# vc_reverb.net
KiCad netlist of a schematic drawn in EAGLE
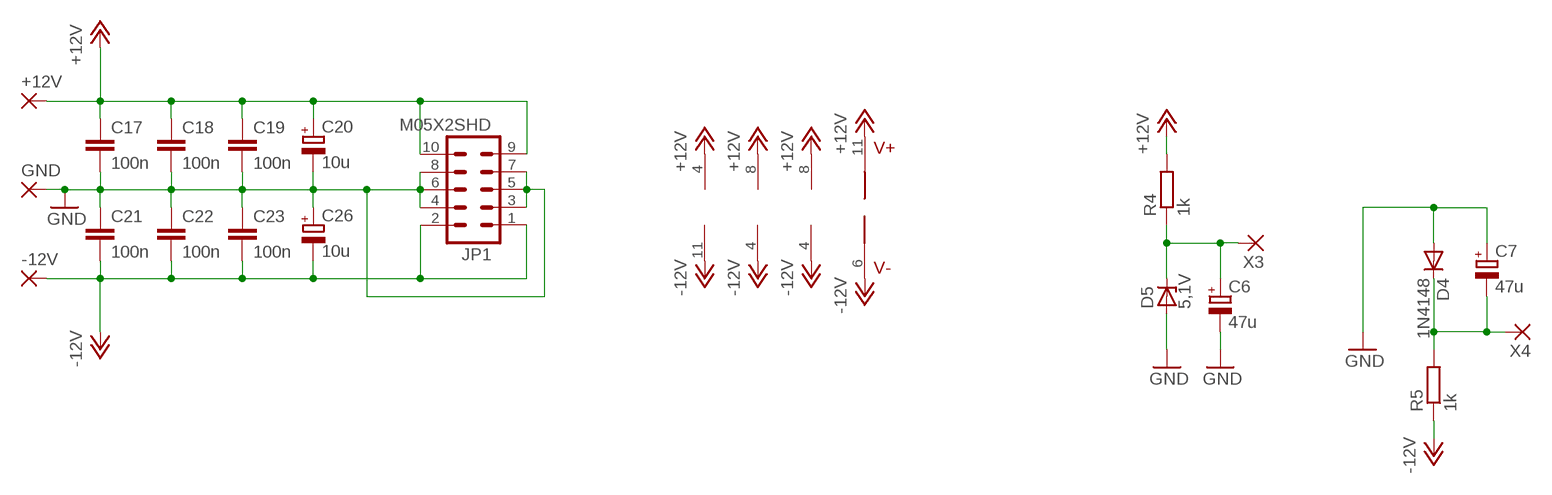
[diagram p0: schematic, sheet 1]
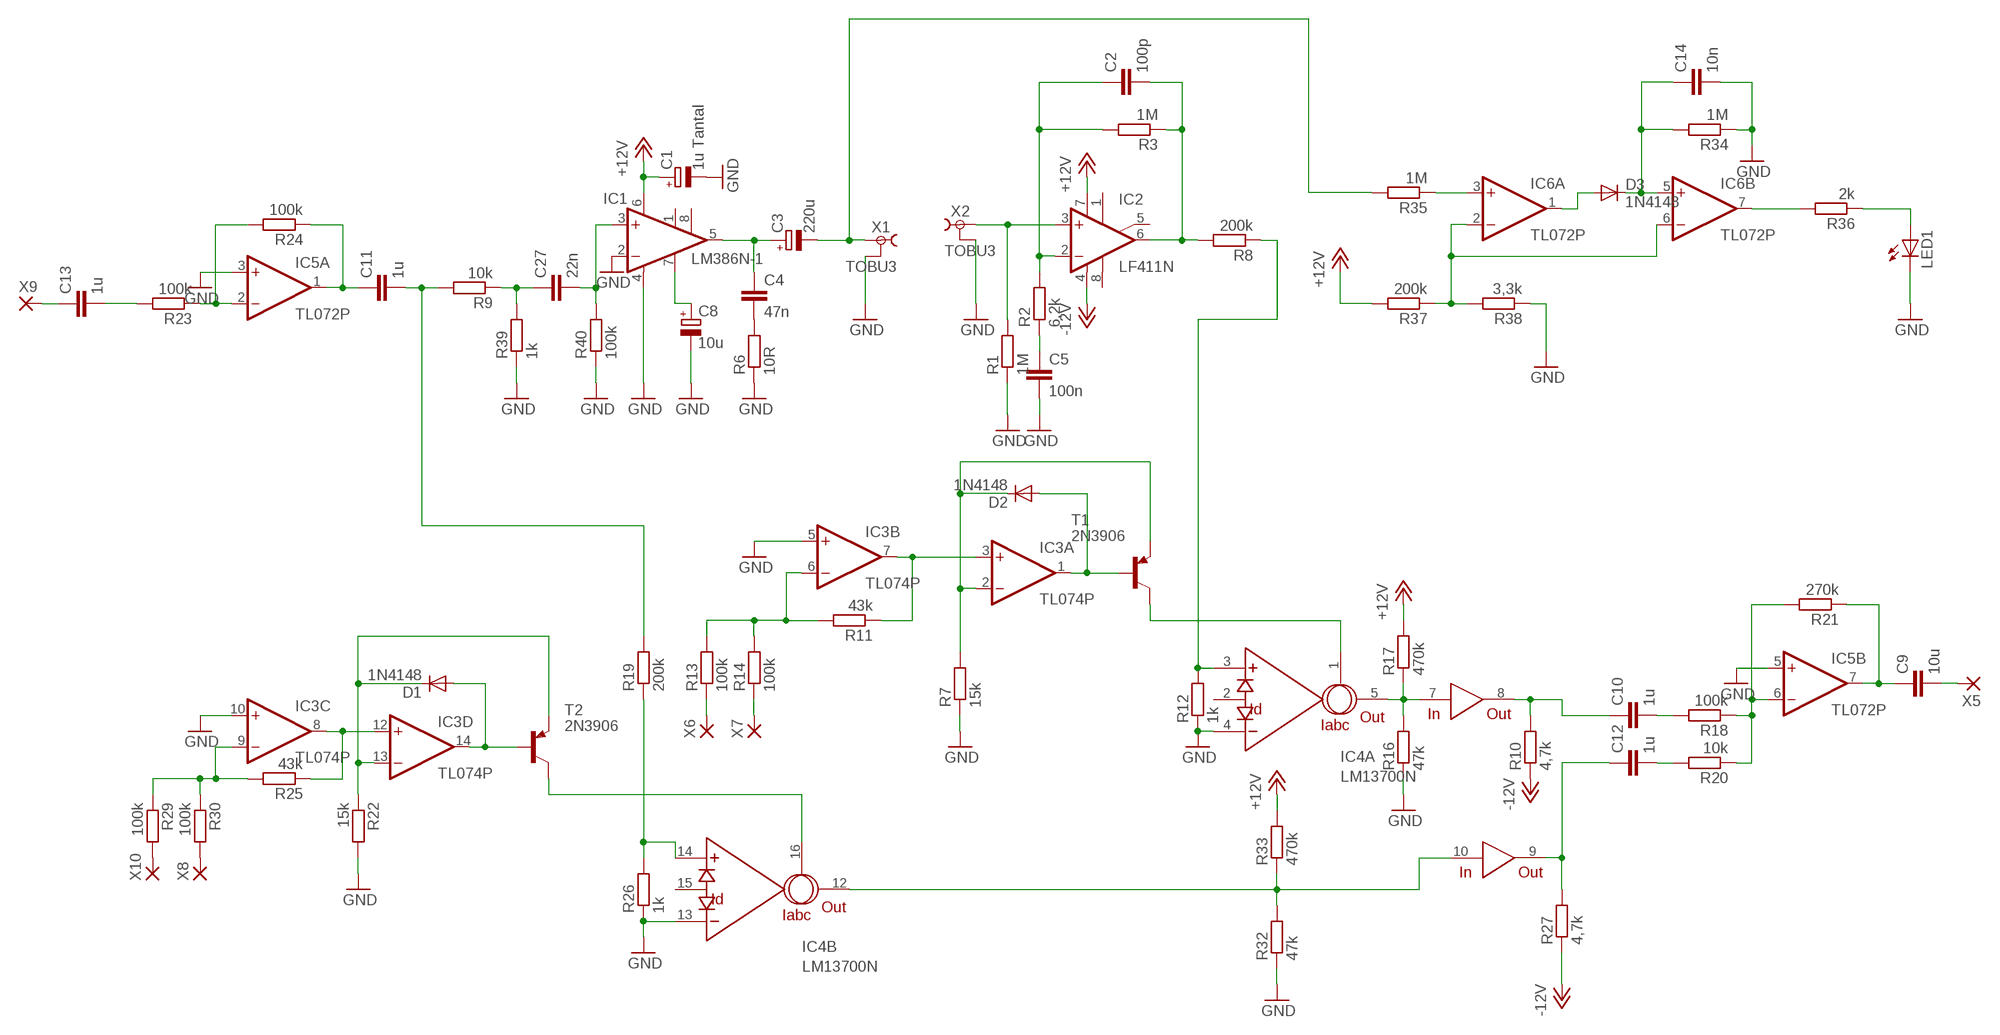
[diagram p1: schematic, sheet 2]

(export (version "E")
  (design (tool "Eeschema 10.0.6"))
  (components
    (comp (ref "C1")
      (value "1u Tantal")
      (footprint "eagle-import:E2-5")
      (libsource (lib "eagle-import") (part "CPOL-EUE2-5"))
    )
    (comp (ref "C2")
      (value "100p")
      (footprint "eagle-import:C050-035X075")
      (libsource (lib "eagle-import") (part "C-EU050-035X075"))
    )
    (comp (ref "C3")
      (value "220u")
      (footprint "eagle-import:E3,5-8")
      (libsource (lib "eagle-import") (part "CPOL-EUE3.5-8"))
    )
    (comp (ref "C4")
      (value "47n")
      (footprint "eagle-import:C050-035X075")
      (libsource (lib "eagle-import") (part "C-EU050-035X075"))
    )
    (comp (ref "C5")
      (value "100n")
      (footprint "eagle-import:C050-035X075")
      (libsource (lib "eagle-import") (part "C-EU050-035X075"))
    )
    (comp (ref "C8")
      (value "10u")
      (footprint "eagle-import:E2-5")
      (libsource (lib "eagle-import") (part "CPOL-EUE2-5"))
    )
    (comp (ref "C9")
      (value "10u")
      (footprint "eagle-import:C050-075X075")
      (libsource (lib "eagle-import") (part "C-EU050-075X075"))
    )
    (comp (ref "C10")
      (value "1u")
      (footprint "eagle-import:C050-050X075")
      (libsource (lib "eagle-import") (part "C-EU050-050X075"))
    )
    (comp (ref "C11")
      (value "1u")
      (footprint "eagle-import:C050-050X075")
      (libsource (lib "eagle-import") (part "C-EU050-050X075"))
    )
    (comp (ref "C12")
      (value "1u")
      (footprint "eagle-import:C050-050X075")
      (libsource (lib "eagle-import") (part "C-EU050-050X075"))
    )
    (comp (ref "C13")
      (value "1u")
      (footprint "eagle-import:C050-050X075")
      (libsource (lib "eagle-import") (part "C-EU050-050X075"))
    )
    (comp (ref "C14")
      (value "10n")
      (footprint "eagle-import:C050-030X075")
      (libsource (lib "eagle-import") (part "C-EU050-030X075"))
    )
    (comp (ref "C27")
      (value "22n")
      (footprint "eagle-import:C050-035X075")
      (libsource (lib "eagle-import") (part "C-EU050-035X075"))
    )
    (comp (ref "D1")
      (value "1N4148")
      (footprint "eagle-import:DO35-7")
      (libsource (lib "eagle-import") (part "1N4148DO35-7"))
    )
    (comp (ref "D2")
      (value "1N4148")
      (footprint "eagle-import:DO35-7")
      (libsource (lib "eagle-import") (part "1N4148DO35-7"))
    )
    (comp (ref "D3")
      (value "1N4148")
      (footprint "eagle-import:DO35-7")
      (libsource (lib "eagle-import") (part "1N4148DO35-7"))
    )
    (comp (ref "IC1")
      (value "LM386N-1")
      (footprint "eagle-import:DIL08")
      (libsource (lib "eagle-import") (part "LM386?-N1"))
    )
    (comp (ref "IC2")
      (value "LF411N")
      (footprint "eagle-import:DIL08")
      (libsource (lib "eagle-import") (part "LF411N"))
    )
    (comp (ref "IC3")
      (value "TL074P")
      (footprint "eagle-import:DIL14")
      (libsource (lib "eagle-import") (part "TL074P"))
    )
    (comp (ref "IC4")
      (value "LM13700N")
      (footprint "eagle-import:DIL16")
      (libsource (lib "eagle-import") (part "LM13700N"))
    )
    (comp (ref "IC5")
      (value "TL072P")
      (footprint "eagle-import:DIL08")
      (libsource (lib "eagle-import") (part "TL072P"))
    )
    (comp (ref "IC6")
      (value "TL072P")
      (footprint "eagle-import:DIL08")
      (libsource (lib "eagle-import") (part "TL072P"))
    )
    (comp (ref "LED1")
      (value "LED5MM")
      (footprint "eagle-import:LED5MM")
      (libsource (lib "eagle-import") (part "LED5MM"))
    )
    (comp (ref "R1")
      (value "1M")
      (footprint "eagle-import:0309V")
      (libsource (lib "eagle-import") (part "R-EU_0309/V"))
    )
    (comp (ref "R2")
      (value "6,2k")
      (footprint "eagle-import:0309V")
      (libsource (lib "eagle-import") (part "R-EU_0309/V"))
    )
    (comp (ref "R3")
      (value "1M")
      (footprint "eagle-import:0309V")
      (libsource (lib "eagle-import") (part "R-EU_0309/V"))
    )
    (comp (ref "R6")
      (value "10R")
      (footprint "eagle-import:0309V")
      (libsource (lib "eagle-import") (part "R-EU_0309/V"))
    )
    (comp (ref "R7")
      (value "15k")
      (footprint "eagle-import:0309V")
      (libsource (lib "eagle-import") (part "R-EU_0309/V"))
    )
    (comp (ref "R8")
      (value "200k")
      (footprint "eagle-import:0309V")
      (libsource (lib "eagle-import") (part "R-EU_0309/V"))
    )
    (comp (ref "R9")
      (value "10k")
      (footprint "eagle-import:0309V")
      (libsource (lib "eagle-import") (part "R-EU_0309/V"))
    )
    (comp (ref "R10")
      (value "4,7k")
      (footprint "eagle-import:0309V")
      (libsource (lib "eagle-import") (part "R-EU_0309/V"))
    )
    (comp (ref "R11")
      (value "43k")
      (footprint "eagle-import:0309V")
      (libsource (lib "eagle-import") (part "R-EU_0309/V"))
    )
    (comp (ref "R12")
      (value "1k")
      (footprint "eagle-import:0309V")
      (libsource (lib "eagle-import") (part "R-EU_0309/V"))
    )
    (comp (ref "R13")
      (value "100k")
      (footprint "eagle-import:0309V")
      (libsource (lib "eagle-import") (part "R-EU_0309/V"))
    )
    (comp (ref "R14")
      (value "100k")
      (footprint "eagle-import:0309V")
      (libsource (lib "eagle-import") (part "R-EU_0309/V"))
    )
    (comp (ref "R16")
      (value "47k")
      (footprint "eagle-import:0309V")
      (libsource (lib "eagle-import") (part "R-EU_0309/V"))
    )
    (comp (ref "R17")
      (value "470k")
      (footprint "eagle-import:0309V")
      (libsource (lib "eagle-import") (part "R-EU_0309/V"))
    )
    (comp (ref "R18")
      (value "100k")
      (footprint "eagle-import:0309V")
      (libsource (lib "eagle-import") (part "R-EU_0309/V"))
    )
    (comp (ref "R19")
      (value "200k")
      (footprint "eagle-import:0309_10")
      (libsource (lib "eagle-import") (part "R-EU_0309/10"))
    )
    (comp (ref "R20")
      (value "10k")
      (footprint "eagle-import:0309V")
      (libsource (lib "eagle-import") (part "R-EU_0309/V"))
    )
    (comp (ref "R21")
      (value "270k")
      (footprint "eagle-import:0309V")
      (libsource (lib "eagle-import") (part "R-EU_0309/V"))
    )
    (comp (ref "R22")
      (value "15k")
      (footprint "eagle-import:0309V")
      (libsource (lib "eagle-import") (part "R-EU_0309/V"))
    )
    (comp (ref "R23")
      (value "100k")
      (footprint "eagle-import:0309V")
      (libsource (lib "eagle-import") (part "R-EU_0309/V"))
    )
    (comp (ref "R24")
      (value "100k")
      (footprint "eagle-import:0309V")
      (libsource (lib "eagle-import") (part "R-EU_0309/V"))
    )
    (comp (ref "R25")
      (value "43k")
      (footprint "eagle-import:0309V")
      (libsource (lib "eagle-import") (part "R-EU_0309/V"))
    )
    (comp (ref "R26")
      (value "1k")
      (footprint "eagle-import:0309V")
      (libsource (lib "eagle-import") (part "R-EU_0309/V"))
    )
    (comp (ref "R27")
      (value "4,7k")
      (footprint "eagle-import:0309V")
      (libsource (lib "eagle-import") (part "R-EU_0309/V"))
    )
    (comp (ref "R29")
      (value "100k")
      (footprint "eagle-import:0309V")
      (libsource (lib "eagle-import") (part "R-EU_0309/V"))
    )
    (comp (ref "R30")
      (value "100k")
      (footprint "eagle-import:0309V")
      (libsource (lib "eagle-import") (part "R-EU_0309/V"))
    )
    (comp (ref "R32")
      (value "47k")
      (footprint "eagle-import:0309V")
      (libsource (lib "eagle-import") (part "R-EU_0309/V"))
    )
    (comp (ref "R33")
      (value "470k")
      (footprint "eagle-import:0309V")
      (libsource (lib "eagle-import") (part "R-EU_0309/V"))
    )
    (comp (ref "R34")
      (value "1M")
      (footprint "eagle-import:0309V")
      (libsource (lib "eagle-import") (part "R-EU_0309/V"))
    )
    (comp (ref "R35")
      (value "1M")
      (footprint "eagle-import:0309V")
      (libsource (lib "eagle-import") (part "R-EU_0309/V"))
    )
    (comp (ref "R36")
      (value "2k")
      (footprint "eagle-import:0309V")
      (libsource (lib "eagle-import") (part "R-EU_0309/V"))
    )
    (comp (ref "R37")
      (value "200k")
      (footprint "eagle-import:0309V")
      (libsource (lib "eagle-import") (part "R-EU_0309/V"))
    )
    (comp (ref "R38")
      (value "3,3k")
      (footprint "eagle-import:0309V")
      (libsource (lib "eagle-import") (part "R-EU_0309/V"))
    )
    (comp (ref "R39")
      (value "1k")
      (footprint "eagle-import:0309V")
      (libsource (lib "eagle-import") (part "R-EU_0309/V"))
    )
    (comp (ref "R40")
      (value "100k")
      (footprint "eagle-import:0309V")
      (libsource (lib "eagle-import") (part "R-EU_0309/V"))
    )
    (comp (ref "T1")
      (value "2N3906")
      (footprint "eagle-import:TO92-EBC")
      (libsource (lib "eagle-import") (part "-PNP-TO92-EBC2N3906"))
    )
    (comp (ref "T2")
      (value "2N3906")
      (footprint "eagle-import:TO92-EBC")
      (libsource (lib "eagle-import") (part "-PNP-TO92-EBC2N3906"))
    )
    (comp (ref "X1")
      (value "TOBU3")
      (footprint "eagle-import:TOBU3")
      (fields (field (name "MF") "FARNELL") (field (name "MPN") "TOBU 3"))
      (libsource (lib "eagle-import") (part "TOBU3"))
    )
    (comp (ref "X2")
      (value "TOBU3")
      (footprint "eagle-import:TOBU3")
      (fields (field (name "MF") "FARNELL") (field (name "MPN") "TOBU 3"))
      (libsource (lib "eagle-import") (part "TOBU3"))
    )
    (comp (ref "X5")
      (value "2,54/1,0")
      (footprint "eagle-import:2,54_1,0")
      (libsource (lib "eagle-import") (part "2,54/1,0"))
    )
    (comp (ref "X6")
      (value "2,54/1,0")
      (footprint "eagle-import:2,54_1,0")
      (libsource (lib "eagle-import") (part "2,54/1,0"))
    )
    (comp (ref "X7")
      (value "2,54/1,0")
      (footprint "eagle-import:2,54_1,0")
      (libsource (lib "eagle-import") (part "2,54/1,0"))
    )
    (comp (ref "X8")
      (value "2,54/1,0")
      (footprint "eagle-import:2,54_1,0")
      (libsource (lib "eagle-import") (part "2,54/1,0"))
    )
    (comp (ref "X9")
      (value "2,54/1,0")
      (footprint "eagle-import:2,54_1,0")
      (libsource (lib "eagle-import") (part "2,54/1,0"))
    )
    (comp (ref "X10")
      (value "2,54/1,0")
      (footprint "eagle-import:2,54_1,0")
      (libsource (lib "eagle-import") (part "2,54/1,0"))
    )
    (comp (ref "+12V")
      (value "2,54/1,0")
      (footprint "eagle-import:2,54_1,0")
      (libsource (lib "eagle-import") (part "2,54/1,0"))
    )
    (comp (ref "-12V")
      (value "2,54/1,0")
      (footprint "eagle-import:2,54_1,0")
      (libsource (lib "eagle-import") (part "2,54/1,0"))
    )
    (comp (ref "C6")
      (value "47u")
      (footprint "eagle-import:E2-5")
      (libsource (lib "eagle-import") (part "CPOL-EUE2-5"))
    )
    (comp (ref "C7")
      (value "47u")
      (footprint "eagle-import:E2-5")
      (libsource (lib "eagle-import") (part "CPOL-EUE2-5"))
    )
    (comp (ref "C17")
      (value "100n")
      (footprint "eagle-import:C025-025X050")
      (libsource (lib "eagle-import") (part "C-EU025-025X050"))
    )
    (comp (ref "C18")
      (value "100n")
      (footprint "eagle-import:C050-035X075")
      (libsource (lib "eagle-import") (part "C-EU050-035X075"))
    )
    (comp (ref "C19")
      (value "100n")
      (footprint "eagle-import:C025-025X050")
      (libsource (lib "eagle-import") (part "C-EU025-025X050"))
    )
    (comp (ref "C20")
      (value "10u")
      (footprint "eagle-import:E2-5")
      (libsource (lib "eagle-import") (part "CPOL-EUE2-5"))
    )
    (comp (ref "C21")
      (value "100n")
      (footprint "eagle-import:C025-025X050")
      (libsource (lib "eagle-import") (part "C-EU025-025X050"))
    )
    (comp (ref "C22")
      (value "100n")
      (footprint "eagle-import:C050-035X075")
      (libsource (lib "eagle-import") (part "C-EU050-035X075"))
    )
    (comp (ref "C23")
      (value "100n")
      (footprint "eagle-import:C025-025X050")
      (libsource (lib "eagle-import") (part "C-EU025-025X050"))
    )
    (comp (ref "C26")
      (value "10u")
      (footprint "eagle-import:E2-5")
      (libsource (lib "eagle-import") (part "CPOL-EUE2-5"))
    )
    (comp (ref "D4")
      (value "1N4148")
      (footprint "eagle-import:DO35-7")
      (libsource (lib "eagle-import") (part "1N4148DO35-7"))
    )
    (comp (ref "D5")
      (value "5,1V")
      (footprint "eagle-import:DO34Z7")
      (libsource (lib "eagle-import") (part "ZENER-DIODEDO34-7"))
    )
    (comp (ref "GND")
      (value "2,54/1,0")
      (footprint "eagle-import:2,54_1,0")
      (libsource (lib "eagle-import") (part "2,54/1,0"))
    )
    (comp (ref "JP1")
      (value "M05X2SHD")
      (footprint "eagle-import:2X5-SHROUDED")
      (libsource (lib "eagle-import") (part "M05X2SHD"))
    )
    (comp (ref "R4")
      (value "1k")
      (footprint "eagle-import:0309V")
      (libsource (lib "eagle-import") (part "R-EU_0309/V"))
    )
    (comp (ref "R5")
      (value "1k")
      (footprint "eagle-import:0309V")
      (libsource (lib "eagle-import") (part "R-EU_0309/V"))
    )
    (comp (ref "X3")
      (value "2,54/1,0")
      (footprint "eagle-import:2,54_1,0")
      (libsource (lib "eagle-import") (part "2,54/1,0"))
    )
    (comp (ref "X4")
      (value "2,54/1,0")
      (footprint "eagle-import:2,54_1,0")
      (libsource (lib "eagle-import") (part "2,54/1,0"))
    )
  )
  (nets
    (net (code "1") (name "+12V") (class "Default")
      (node (ref "+12V") (pin "1") (pinfunction "P_1") (pintype "passive"))
      (node (ref "C1") (pin "+") (pinfunction "+_+") (pintype "passive"))
      (node (ref "C17") (pin "1") (pinfunction "1_1") (pintype "passive"))
      (node (ref "C18") (pin "1") (pinfunction "1_1") (pintype "passive"))
      (node (ref "C19") (pin "1") (pinfunction "1_1") (pintype "passive"))
      (node (ref "C20") (pin "+") (pinfunction "+_+") (pintype "passive"))
      (node (ref "IC1") (pin "6") (pinfunction "VS_6") (pintype "power_in"))
      (node (ref "IC2") (pin "7") (pinfunction "V+_7") (pintype "power_in"))
      (node (ref "IC3") (pin "4") (pinfunction "V+_4") (pintype "power_in"))
      (node (ref "IC4") (pin "11") (pinfunction "V+_11") (pintype "bidirectional"))
      (node (ref "IC5") (pin "8") (pinfunction "V+_8") (pintype "power_in"))
      (node (ref "IC6") (pin "8") (pinfunction "V+_8") (pintype "power_in"))
      (node (ref "JP1") (pin "10") (pinfunction "10_10") (pintype "passive"))
      (node (ref "JP1") (pin "9") (pinfunction "9_9") (pintype "passive"))
      (node (ref "R17") (pin "2") (pinfunction "2_2") (pintype "passive"))
      (node (ref "R33") (pin "2") (pinfunction "2_2") (pintype "passive"))
      (node (ref "R37") (pin "2") (pinfunction "2_2") (pintype "passive"))
      (node (ref "R4") (pin "2") (pinfunction "2_2") (pintype "passive"))
    )
    (net (code "2") (name "-12V") (class "Default")
      (node (ref "-12V") (pin "1") (pinfunction "P_1") (pintype "passive"))
      (node (ref "C21") (pin "2") (pinfunction "2_2") (pintype "passive"))
      (node (ref "C22") (pin "2") (pinfunction "2_2") (pintype "passive"))
      (node (ref "C23") (pin "2") (pinfunction "2_2") (pintype "passive"))
      (node (ref "C26") (pin "-") (pinfunction "-_-") (pintype "passive"))
      (node (ref "IC2") (pin "4") (pinfunction "V-_4") (pintype "power_in"))
      (node (ref "IC3") (pin "11") (pinfunction "V-_11") (pintype "power_in"))
      (node (ref "IC4") (pin "6") (pinfunction "V-_6") (pintype "bidirectional"))
      (node (ref "IC5") (pin "4") (pinfunction "V-_4") (pintype "power_in"))
      (node (ref "IC6") (pin "4") (pinfunction "V-_4") (pintype "power_in"))
      (node (ref "JP1") (pin "1") (pinfunction "1_1") (pintype "passive"))
      (node (ref "JP1") (pin "2") (pinfunction "2_2") (pintype "passive"))
      (node (ref "R10") (pin "1") (pinfunction "1_1") (pintype "passive"))
      (node (ref "R27") (pin "1") (pinfunction "1_1") (pintype "passive"))
      (node (ref "R5") (pin "1") (pinfunction "1_1") (pintype "passive"))
    )
    (net (code "3") (name "GND") (class "Default")
      (node (ref "C1") (pin "-") (pinfunction "-_-") (pintype "passive"))
      (node (ref "C14") (pin "2") (pinfunction "2_2") (pintype "passive"))
      (node (ref "C17") (pin "2") (pinfunction "2_2") (pintype "passive"))
      (node (ref "C18") (pin "2") (pinfunction "2_2") (pintype "passive"))
      (node (ref "C19") (pin "2") (pinfunction "2_2") (pintype "passive"))
      (node (ref "C20") (pin "-") (pinfunction "-_-") (pintype "passive"))
      (node (ref "C21") (pin "1") (pinfunction "1_1") (pintype "passive"))
      (node (ref "C22") (pin "1") (pinfunction "1_1") (pintype "passive"))
      (node (ref "C23") (pin "1") (pinfunction "1_1") (pintype "passive"))
      (node (ref "C26") (pin "+") (pinfunction "+_+") (pintype "passive"))
      (node (ref "C5") (pin "2") (pinfunction "2_2") (pintype "passive"))
      (node (ref "C6") (pin "-") (pinfunction "-_-") (pintype "passive"))
      (node (ref "C7") (pin "+") (pinfunction "+_+") (pintype "passive"))
      (node (ref "C8") (pin "-") (pinfunction "-_-") (pintype "passive"))
      (node (ref "D4") (pin "A") (pinfunction "A_A") (pintype "passive"))
      (node (ref "D5") (pin "A") (pinfunction "A_A") (pintype "passive"))
      (node (ref "GND") (pin "1") (pinfunction "P_1") (pintype "passive"))
      (node (ref "IC1") (pin "2") (pinfunction "-IN_2") (pintype "input"))
      (node (ref "IC1") (pin "4") (pinfunction "GND_4") (pintype "power_in"))
      (node (ref "IC3") (pin "10") (pinfunction "+IN_10") (pintype "input"))
      (node (ref "IC3") (pin "5") (pinfunction "+IN_5") (pintype "input"))
      (node (ref "IC4") (pin "13") (pinfunction "-IN_13") (pintype "bidirectional"))
      (node (ref "IC4") (pin "4") (pinfunction "-IN_4") (pintype "bidirectional"))
      (node (ref "IC5") (pin "3") (pinfunction "+IN_3") (pintype "input"))
      (node (ref "IC5") (pin "5") (pinfunction "+IN_5") (pintype "input"))
      (node (ref "JP1") (pin "3") (pinfunction "3_3") (pintype "passive"))
      (node (ref "JP1") (pin "4") (pinfunction "4_4") (pintype "passive"))
      (node (ref "JP1") (pin "5") (pinfunction "5_5") (pintype "passive"))
      (node (ref "JP1") (pin "6") (pinfunction "6_6") (pintype "passive"))
      (node (ref "JP1") (pin "7") (pinfunction "7_7") (pintype "passive"))
      (node (ref "JP1") (pin "8") (pinfunction "8_8") (pintype "passive"))
      (node (ref "LED1") (pin "K") (pinfunction "C_K") (pintype "passive"))
      (node (ref "R1") (pin "1") (pinfunction "1_1") (pintype "passive"))
      (node (ref "R12") (pin "1") (pinfunction "1_1") (pintype "passive"))
      (node (ref "R16") (pin "1") (pinfunction "1_1") (pintype "passive"))
      (node (ref "R22") (pin "2") (pinfunction "2_2") (pintype "passive"))
      (node (ref "R26") (pin "1") (pinfunction "1_1") (pintype "passive"))
      (node (ref "R32") (pin "1") (pinfunction "1_1") (pintype "passive"))
      (node (ref "R34") (pin "1") (pinfunction "1_1") (pintype "passive"))
      (node (ref "R38") (pin "1") (pinfunction "1_1") (pintype "passive"))
      (node (ref "R39") (pin "1") (pinfunction "1_1") (pintype "passive"))
      (node (ref "R40") (pin "1") (pinfunction "1_1") (pintype "passive"))
      (node (ref "R6") (pin "1") (pinfunction "1_1") (pintype "passive"))
      (node (ref "R7") (pin "1") (pinfunction "1_1") (pintype "passive"))
      (node (ref "X1") (pin "2") (pinfunction "2_2") (pintype "passive"))
      (node (ref "X1") (pin "2@1") (pinfunction "2_2@1") (pintype "passive"))
      (node (ref "X1") (pin "2@2") (pinfunction "2_2@2") (pintype "passive"))
      (node (ref "X2") (pin "2") (pinfunction "2_2") (pintype "passive"))
      (node (ref "X2") (pin "2@1") (pinfunction "2_2@1") (pintype "passive"))
      (node (ref "X2") (pin "2@2") (pinfunction "2_2@2") (pintype "passive"))
    )
    (net (code "4") (name "Net-(C3-Pad-)") (class "Default")
      (node (ref "C3") (pin "-") (pinfunction "-_-") (pintype "passive"))
      (node (ref "R35") (pin "2") (pinfunction "2_2") (pintype "passive"))
      (node (ref "X1") (pin "1") (pinfunction "1_1") (pintype "passive"))
    )
    (net (code "5") (name "Net-(C4-Pad2)") (class "Default")
      (node (ref "C4") (pin "2") (pinfunction "2_2") (pintype "passive"))
      (node (ref "R6") (pin "2") (pinfunction "2_2") (pintype "passive"))
    )
    (net (code "6") (name "Net-(C5-Pad1)") (class "Default")
      (node (ref "C5") (pin "1") (pinfunction "1_1") (pintype "passive"))
      (node (ref "R2") (pin "1") (pinfunction "1_1") (pintype "passive"))
    )
    (net (code "7") (name "Net-(C10-Pad2)") (class "Default")
      (node (ref "C10") (pin "2") (pinfunction "2_2") (pintype "passive"))
      (node (ref "R18") (pin "2") (pinfunction "2_2") (pintype "passive"))
    )
    (net (code "8") (name "Net-(C11-Pad2)") (class "Default")
      (node (ref "C11") (pin "2") (pinfunction "2_2") (pintype "passive"))
      (node (ref "R19") (pin "2") (pinfunction "2_2") (pintype "passive"))
      (node (ref "R9") (pin "2") (pinfunction "2_2") (pintype "passive"))
    )
    (net (code "9") (name "Net-(C12-Pad2)") (class "Default")
      (node (ref "C12") (pin "2") (pinfunction "2_2") (pintype "passive"))
      (node (ref "R20") (pin "2") (pinfunction "2_2") (pintype "passive"))
    )
    (net (code "10") (name "Net-(C13-Pad2)") (class "Default")
      (node (ref "C13") (pin "2") (pinfunction "2_2") (pintype "passive"))
      (node (ref "R23") (pin "2") (pinfunction "2_2") (pintype "passive"))
    )
    (net (code "11") (name "Net-(C27-Pad1)") (class "Default")
      (node (ref "C27") (pin "1") (pinfunction "1_1") (pintype "passive"))
      (node (ref "R39") (pin "2") (pinfunction "2_2") (pintype "passive"))
      (node (ref "R9") (pin "1") (pinfunction "1_1") (pintype "passive"))
    )
    (net (code "12") (name "Net-(IC1-+IN)") (class "Default")
      (node (ref "C27") (pin "2") (pinfunction "2_2") (pintype "passive"))
      (node (ref "IC1") (pin "3") (pinfunction "+IN_3") (pintype "input"))
      (node (ref "R40") (pin "2") (pinfunction "2_2") (pintype "passive"))
    )
    (net (code "13") (name "Net-(IC1-BYPASS)") (class "Default")
      (node (ref "C8") (pin "+") (pinfunction "+_+") (pintype "passive"))
      (node (ref "IC1") (pin "7") (pinfunction "BYPASS_7") (pintype "passive"))
    )
    (net (code "14") (name "Net-(IC1-OUT)") (class "Default")
      (node (ref "C3") (pin "+") (pinfunction "+_+") (pintype "passive"))
      (node (ref "C4") (pin "1") (pinfunction "1_1") (pintype "passive"))
      (node (ref "IC1") (pin "5") (pinfunction "OUT_5") (pintype "output"))
    )
    (net (code "15") (name "Net-(IC2-+IN)") (class "Default")
      (node (ref "IC2") (pin "3") (pinfunction "+IN_3") (pintype "input"))
      (node (ref "R1") (pin "2") (pinfunction "2_2") (pintype "passive"))
      (node (ref "X2") (pin "1") (pinfunction "1_1") (pintype "passive"))
    )
    (net (code "16") (name "Net-(IC2--IN)") (class "Default")
      (node (ref "C2") (pin "1") (pinfunction "1_1") (pintype "passive"))
      (node (ref "IC2") (pin "2") (pinfunction "-IN_2") (pintype "input"))
      (node (ref "R2") (pin "2") (pinfunction "2_2") (pintype "passive"))
      (node (ref "R3") (pin "2") (pinfunction "2_2") (pintype "passive"))
    )
    (net (code "17") (name "Net-(IC2-OUT)") (class "Default")
      (node (ref "C2") (pin "2") (pinfunction "2_2") (pintype "passive"))
      (node (ref "IC2") (pin "6") (pinfunction "OUT_6") (pintype "output"))
      (node (ref "R3") (pin "1") (pinfunction "1_1") (pintype "passive"))
      (node (ref "R8") (pin "2") (pinfunction "2_2") (pintype "passive"))
    )
    (net (code "18") (name "Net-(IC3A-+IN)") (class "Default")
      (node (ref "IC3") (pin "3") (pinfunction "+IN_3") (pintype "input"))
      (node (ref "IC3") (pin "7") (pinfunction "OUT_7") (pintype "output"))
      (node (ref "R11") (pin "1") (pinfunction "1_1") (pintype "passive"))
    )
    (net (code "19") (name "Net-(IC3A--IN)") (class "Default")
      (node (ref "D2") (pin "C") (pinfunction "C_C") (pintype "passive"))
      (node (ref "IC3") (pin "2") (pinfunction "-IN_2") (pintype "input"))
      (node (ref "R7") (pin "2") (pinfunction "2_2") (pintype "passive"))
      (node (ref "T1") (pin "E") (pinfunction "E_E") (pintype "passive"))
    )
    (net (code "20") (name "Net-(IC3A-OUT)") (class "Default")
      (node (ref "D2") (pin "A") (pinfunction "A_A") (pintype "passive"))
      (node (ref "IC3") (pin "1") (pinfunction "OUT_1") (pintype "output"))
      (node (ref "T1") (pin "B") (pinfunction "B_B") (pintype "passive"))
    )
    (net (code "21") (name "Net-(IC3B--IN)") (class "Default")
      (node (ref "IC3") (pin "6") (pinfunction "-IN_6") (pintype "input"))
      (node (ref "R11") (pin "2") (pinfunction "2_2") (pintype "passive"))
      (node (ref "R13") (pin "2") (pinfunction "2_2") (pintype "passive"))
      (node (ref "R14") (pin "2") (pinfunction "2_2") (pintype "passive"))
    )
    (net (code "22") (name "Net-(IC3C--IN)") (class "Default")
      (node (ref "IC3") (pin "9") (pinfunction "-IN_9") (pintype "input"))
      (node (ref "R25") (pin "2") (pinfunction "2_2") (pintype "passive"))
      (node (ref "R29") (pin "1") (pinfunction "1_1") (pintype "passive"))
      (node (ref "R30") (pin "1") (pinfunction "1_1") (pintype "passive"))
    )
    (net (code "23") (name "Net-(IC3C-OUT)") (class "Default")
      (node (ref "IC3") (pin "12") (pinfunction "+IN_12") (pintype "input"))
      (node (ref "IC3") (pin "8") (pinfunction "OUT_8") (pintype "output"))
      (node (ref "R25") (pin "1") (pinfunction "1_1") (pintype "passive"))
    )
    (net (code "24") (name "Net-(IC3D--IN)") (class "Default")
      (node (ref "D1") (pin "C") (pinfunction "C_C") (pintype "passive"))
      (node (ref "IC3") (pin "13") (pinfunction "-IN_13") (pintype "input"))
      (node (ref "R22") (pin "1") (pinfunction "1_1") (pintype "passive"))
      (node (ref "T2") (pin "E") (pinfunction "E_E") (pintype "passive"))
    )
    (net (code "25") (name "Net-(IC3D-OUT)") (class "Default")
      (node (ref "D1") (pin "A") (pinfunction "A_A") (pintype "passive"))
      (node (ref "IC3") (pin "14") (pinfunction "OUT_14") (pintype "output"))
      (node (ref "T2") (pin "B") (pinfunction "B_B") (pintype "passive"))
    )
    (net (code "26") (name "Net-(IC4A-+IN)") (class "Default")
      (node (ref "IC4") (pin "3") (pinfunction "+IN_3") (pintype "bidirectional"))
      (node (ref "R12") (pin "2") (pinfunction "2_2") (pintype "passive"))
      (node (ref "R8") (pin "1") (pinfunction "1_1") (pintype "passive"))
    )
    (net (code "27") (name "Net-(IC4A-IABC)") (class "Default")
      (node (ref "IC4") (pin "1") (pinfunction "IABC_1") (pintype "bidirectional"))
      (node (ref "T1") (pin "C") (pinfunction "C_C") (pintype "passive"))
    )
    (net (code "28") (name "Net-(IC4A-OUT)") (class "Default")
      (node (ref "IC4") (pin "5") (pinfunction "OUT_5") (pintype "bidirectional"))
      (node (ref "IC4") (pin "7") (pinfunction "IN_7") (pintype "bidirectional"))
      (node (ref "R16") (pin "2") (pinfunction "2_2") (pintype "passive"))
      (node (ref "R17") (pin "1") (pinfunction "1_1") (pintype "passive"))
    )
    (net (code "29") (name "Net-(IC4B-+IN)") (class "Default")
      (node (ref "IC4") (pin "14") (pinfunction "+IN_14") (pintype "bidirectional"))
      (node (ref "R19") (pin "1") (pinfunction "1_1") (pintype "passive"))
      (node (ref "R26") (pin "2") (pinfunction "2_2") (pintype "passive"))
    )
    (net (code "30") (name "Net-(IC4B-IABC)") (class "Default")
      (node (ref "IC4") (pin "16") (pinfunction "IABC_16") (pintype "bidirectional"))
      (node (ref "T2") (pin "C") (pinfunction "C_C") (pintype "passive"))
    )
    (net (code "31") (name "Net-(IC4B-OUT)") (class "Default")
      (node (ref "IC4") (pin "10") (pinfunction "IN_10") (pintype "bidirectional"))
      (node (ref "IC4") (pin "12") (pinfunction "OUT_12") (pintype "bidirectional"))
      (node (ref "R32") (pin "2") (pinfunction "2_2") (pintype "passive"))
      (node (ref "R33") (pin "1") (pinfunction "1_1") (pintype "passive"))
    )
    (net (code "32") (name "Net-(IC4C-OUT)") (class "Default")
      (node (ref "C10") (pin "1") (pinfunction "1_1") (pintype "passive"))
      (node (ref "IC4") (pin "8") (pinfunction "OUT_8") (pintype "bidirectional"))
      (node (ref "R10") (pin "2") (pinfunction "2_2") (pintype "passive"))
    )
    (net (code "33") (name "Net-(IC4D-OUT)") (class "Default")
      (node (ref "C12") (pin "1") (pinfunction "1_1") (pintype "passive"))
      (node (ref "IC4") (pin "9") (pinfunction "OUT_9") (pintype "bidirectional"))
      (node (ref "R27") (pin "2") (pinfunction "2_2") (pintype "passive"))
    )
    (net (code "34") (name "Net-(IC5A--IN)") (class "Default")
      (node (ref "IC5") (pin "2") (pinfunction "-IN_2") (pintype "input"))
      (node (ref "R23") (pin "1") (pinfunction "1_1") (pintype "passive"))
      (node (ref "R24") (pin "2") (pinfunction "2_2") (pintype "passive"))
    )
    (net (code "35") (name "Net-(IC5A-OUT)") (class "Default")
      (node (ref "C11") (pin "1") (pinfunction "1_1") (pintype "passive"))
      (node (ref "IC5") (pin "1") (pinfunction "OUT_1") (pintype "output"))
      (node (ref "R24") (pin "1") (pinfunction "1_1") (pintype "passive"))
    )
    (net (code "36") (name "Net-(IC5B--IN)") (class "Default")
      (node (ref "IC5") (pin "6") (pinfunction "-IN_6") (pintype "input"))
      (node (ref "R18") (pin "1") (pinfunction "1_1") (pintype "passive"))
      (node (ref "R20") (pin "1") (pinfunction "1_1") (pintype "passive"))
      (node (ref "R21") (pin "2") (pinfunction "2_2") (pintype "passive"))
    )
    (net (code "37") (name "Net-(IC5B-OUT)") (class "Default")
      (node (ref "C9") (pin "1") (pinfunction "1_1") (pintype "passive"))
      (node (ref "IC5") (pin "7") (pinfunction "OUT_7") (pintype "output"))
      (node (ref "R21") (pin "1") (pinfunction "1_1") (pintype "passive"))
    )
    (net (code "38") (name "Net-(IC6A-+IN)") (class "Default")
      (node (ref "IC6") (pin "3") (pinfunction "+IN_3") (pintype "input"))
      (node (ref "R35") (pin "1") (pinfunction "1_1") (pintype "passive"))
    )
    (net (code "39") (name "Net-(IC6A--IN)") (class "Default")
      (node (ref "IC6") (pin "2") (pinfunction "-IN_2") (pintype "input"))
      (node (ref "IC6") (pin "6") (pinfunction "-IN_6") (pintype "input"))
      (node (ref "R37") (pin "1") (pinfunction "1_1") (pintype "passive"))
      (node (ref "R38") (pin "2") (pinfunction "2_2") (pintype "passive"))
    )
    (net (code "40") (name "Net-(IC6A-OUT)") (class "Default")
      (node (ref "D3") (pin "A") (pinfunction "A_A") (pintype "passive"))
      (node (ref "IC6") (pin "1") (pinfunction "OUT_1") (pintype "output"))
    )
    (net (code "41") (name "Net-(IC6B-+IN)") (class "Default")
      (node (ref "C14") (pin "1") (pinfunction "1_1") (pintype "passive"))
      (node (ref "D3") (pin "C") (pinfunction "C_C") (pintype "passive"))
      (node (ref "IC6") (pin "5") (pinfunction "+IN_5") (pintype "input"))
      (node (ref "R34") (pin "2") (pinfunction "2_2") (pintype "passive"))
    )
    (net (code "42") (name "Net-(IC6B-OUT)") (class "Default")
      (node (ref "IC6") (pin "7") (pinfunction "OUT_7") (pintype "output"))
      (node (ref "R36") (pin "2") (pinfunction "2_2") (pintype "passive"))
    )
    (net (code "43") (name "Net-(LED1-PadA)") (class "Default")
      (node (ref "LED1") (pin "A") (pinfunction "A_A") (pintype "passive"))
      (node (ref "R36") (pin "1") (pinfunction "1_1") (pintype "passive"))
    )
    (net (code "44") (name "Net-(X3-P)") (class "Default")
      (node (ref "C6") (pin "+") (pinfunction "+_+") (pintype "passive"))
      (node (ref "D5") (pin "C") (pinfunction "C_C") (pintype "passive"))
      (node (ref "R4") (pin "1") (pinfunction "1_1") (pintype "passive"))
      (node (ref "X3") (pin "1") (pinfunction "P_1") (pintype "passive"))
    )
    (net (code "45") (name "Net-(X4-P)") (class "Default")
      (node (ref "C7") (pin "-") (pinfunction "-_-") (pintype "passive"))
      (node (ref "D4") (pin "C") (pinfunction "C_C") (pintype "passive"))
      (node (ref "R5") (pin "2") (pinfunction "2_2") (pintype "passive"))
      (node (ref "X4") (pin "1") (pinfunction "P_1") (pintype "passive"))
    )
    (net (code "46") (name "Net-(X5-P)") (class "Default")
      (node (ref "C9") (pin "2") (pinfunction "2_2") (pintype "passive"))
      (node (ref "X5") (pin "1") (pinfunction "P_1") (pintype "passive"))
    )
    (net (code "47") (name "Net-(X6-P)") (class "Default")
      (node (ref "R13") (pin "1") (pinfunction "1_1") (pintype "passive"))
      (node (ref "X6") (pin "1") (pinfunction "P_1") (pintype "passive"))
    )
    (net (code "48") (name "Net-(X7-P)") (class "Default")
      (node (ref "R14") (pin "1") (pinfunction "1_1") (pintype "passive"))
      (node (ref "X7") (pin "1") (pinfunction "P_1") (pintype "passive"))
    )
    (net (code "49") (name "Net-(X8-P)") (class "Default")
      (node (ref "R30") (pin "2") (pinfunction "2_2") (pintype "passive"))
      (node (ref "X8") (pin "1") (pinfunction "P_1") (pintype "passive"))
    )
    (net (code "50") (name "Net-(X9-P)") (class "Default")
      (node (ref "C13") (pin "1") (pinfunction "1_1") (pintype "passive"))
      (node (ref "X9") (pin "1") (pinfunction "P_1") (pintype "passive"))
    )
    (net (code "51") (name "Net-(X10-P)") (class "Default")
      (node (ref "R29") (pin "2") (pinfunction "2_2") (pintype "passive"))
      (node (ref "X10") (pin "1") (pinfunction "P_1") (pintype "passive"))
    )
    (net (code "52") (name "unconnected-(IC1-GAIN-Pad1)") (class "Default")
      (node (ref "IC1") (pin "1") (pinfunction "GAIN_1") (pintype "passive"))
    )
    (net (code "53") (name "unconnected-(IC1-GAIN-Pad8)") (class "Default")
      (node (ref "IC1") (pin "8") (pinfunction "GAIN_8") (pintype "passive"))
    )
    (net (code "54") (name "unconnected-(IC2-ON1-Pad1)") (class "Default")
      (node (ref "IC2") (pin "1") (pinfunction "ON1_1") (pintype "passive"))
    )
    (net (code "55") (name "unconnected-(IC2-ON2-Pad5)") (class "Default")
      (node (ref "IC2") (pin "5") (pinfunction "ON2_5") (pintype "passive"))
    )
    (net (code "56") (name "unconnected-(IC2-OPT-Pad8)") (class "Default")
      (node (ref "IC2") (pin "8") (pinfunction "OPT_8") (pintype "passive"))
    )
    (net (code "57") (name "unconnected-(IC4A-ID-Pad2)") (class "Default")
      (node (ref "IC4") (pin "2") (pinfunction "ID_2") (pintype "bidirectional"))
    )
    (net (code "58") (name "unconnected-(IC4B-ID-Pad15)") (class "Default")
      (node (ref "IC4") (pin "15") (pinfunction "ID_15") (pintype "bidirectional"))
    )
  )
)
